# USB_RS232_Adaper_V2.net
KiCad netlist of a schematic drawn in EAGLE
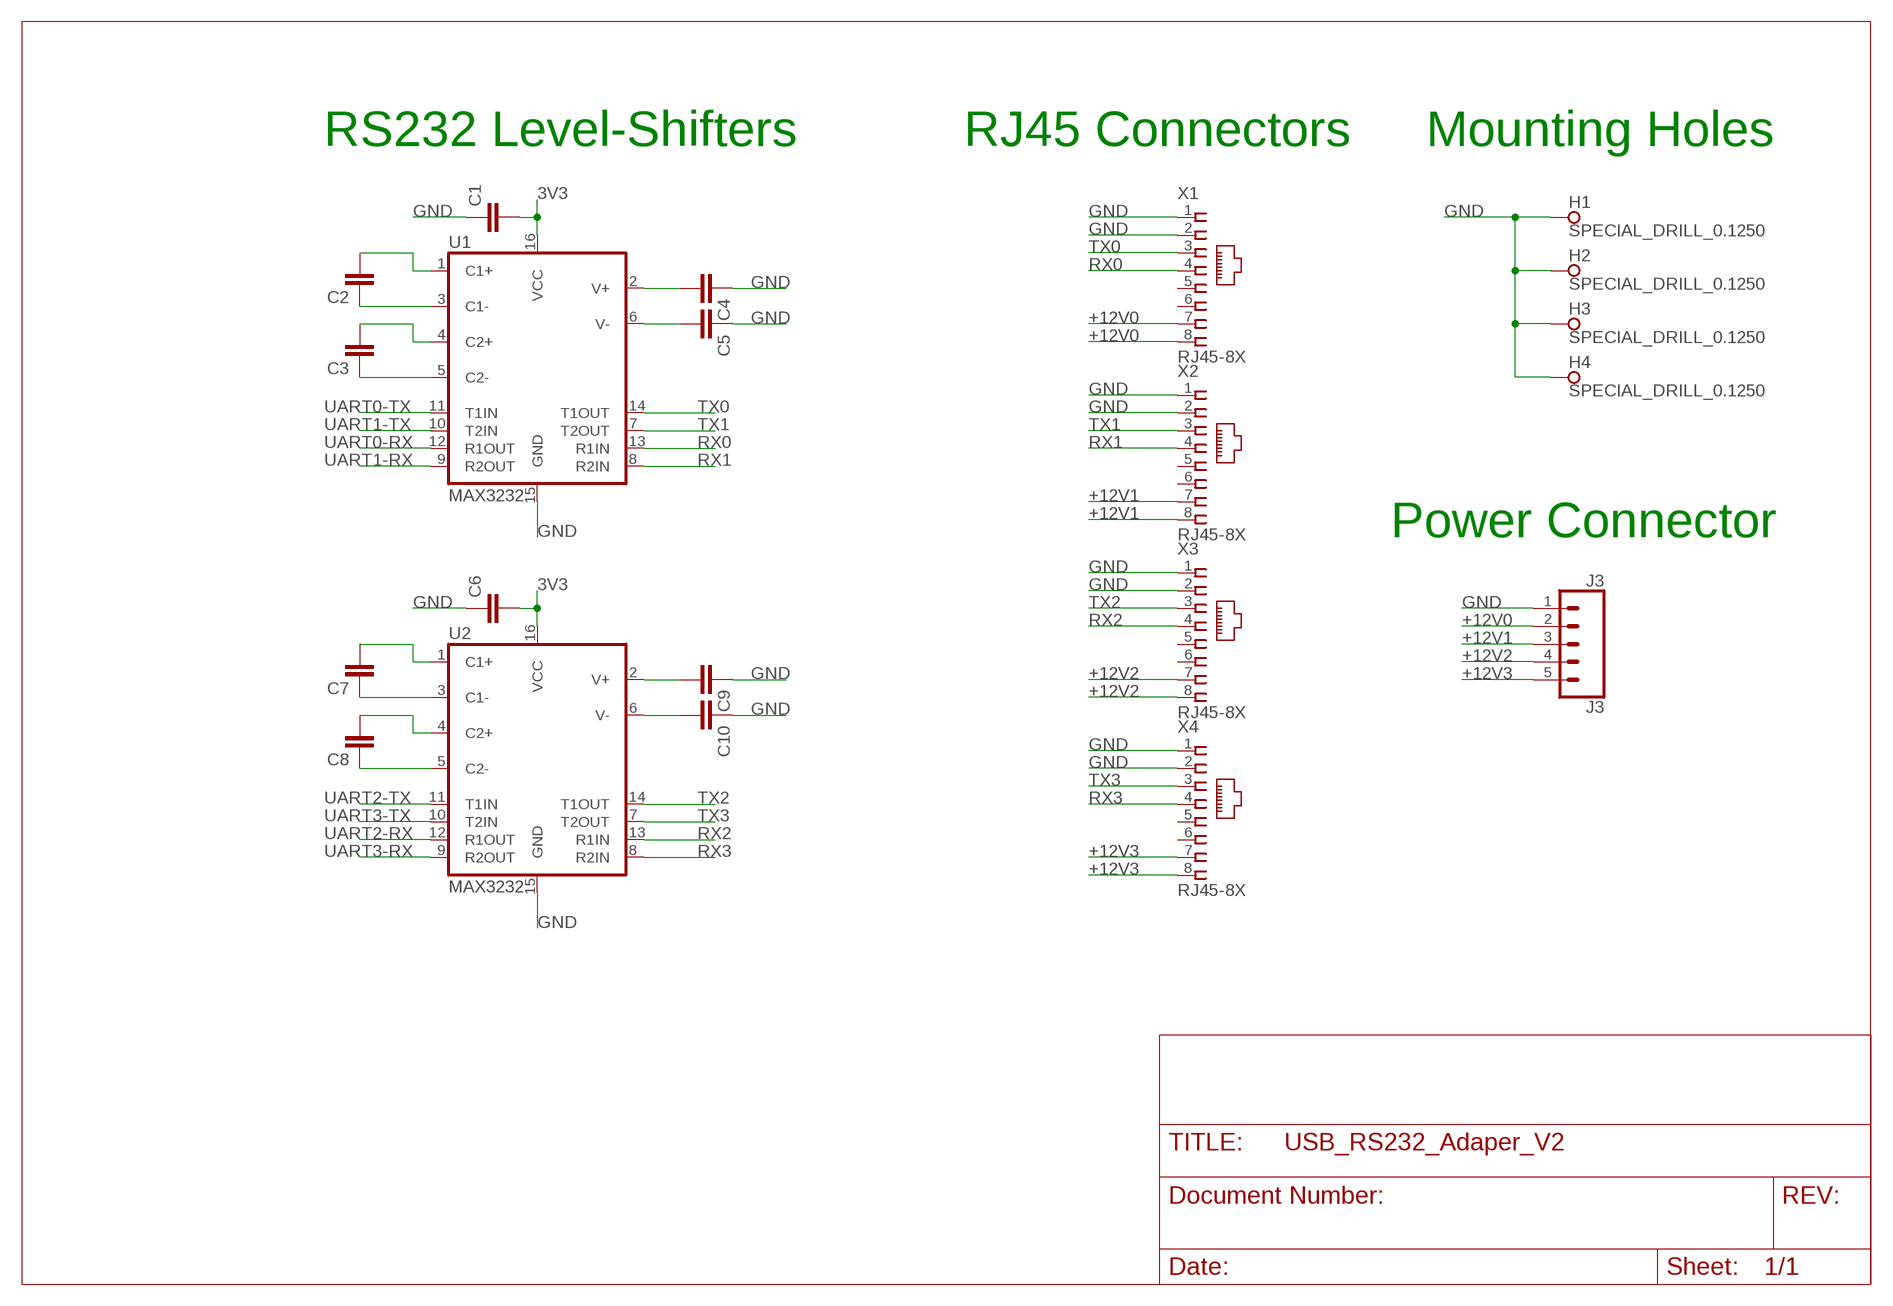
[diagram p0: schematic, sheet 1, part 1 of 2]
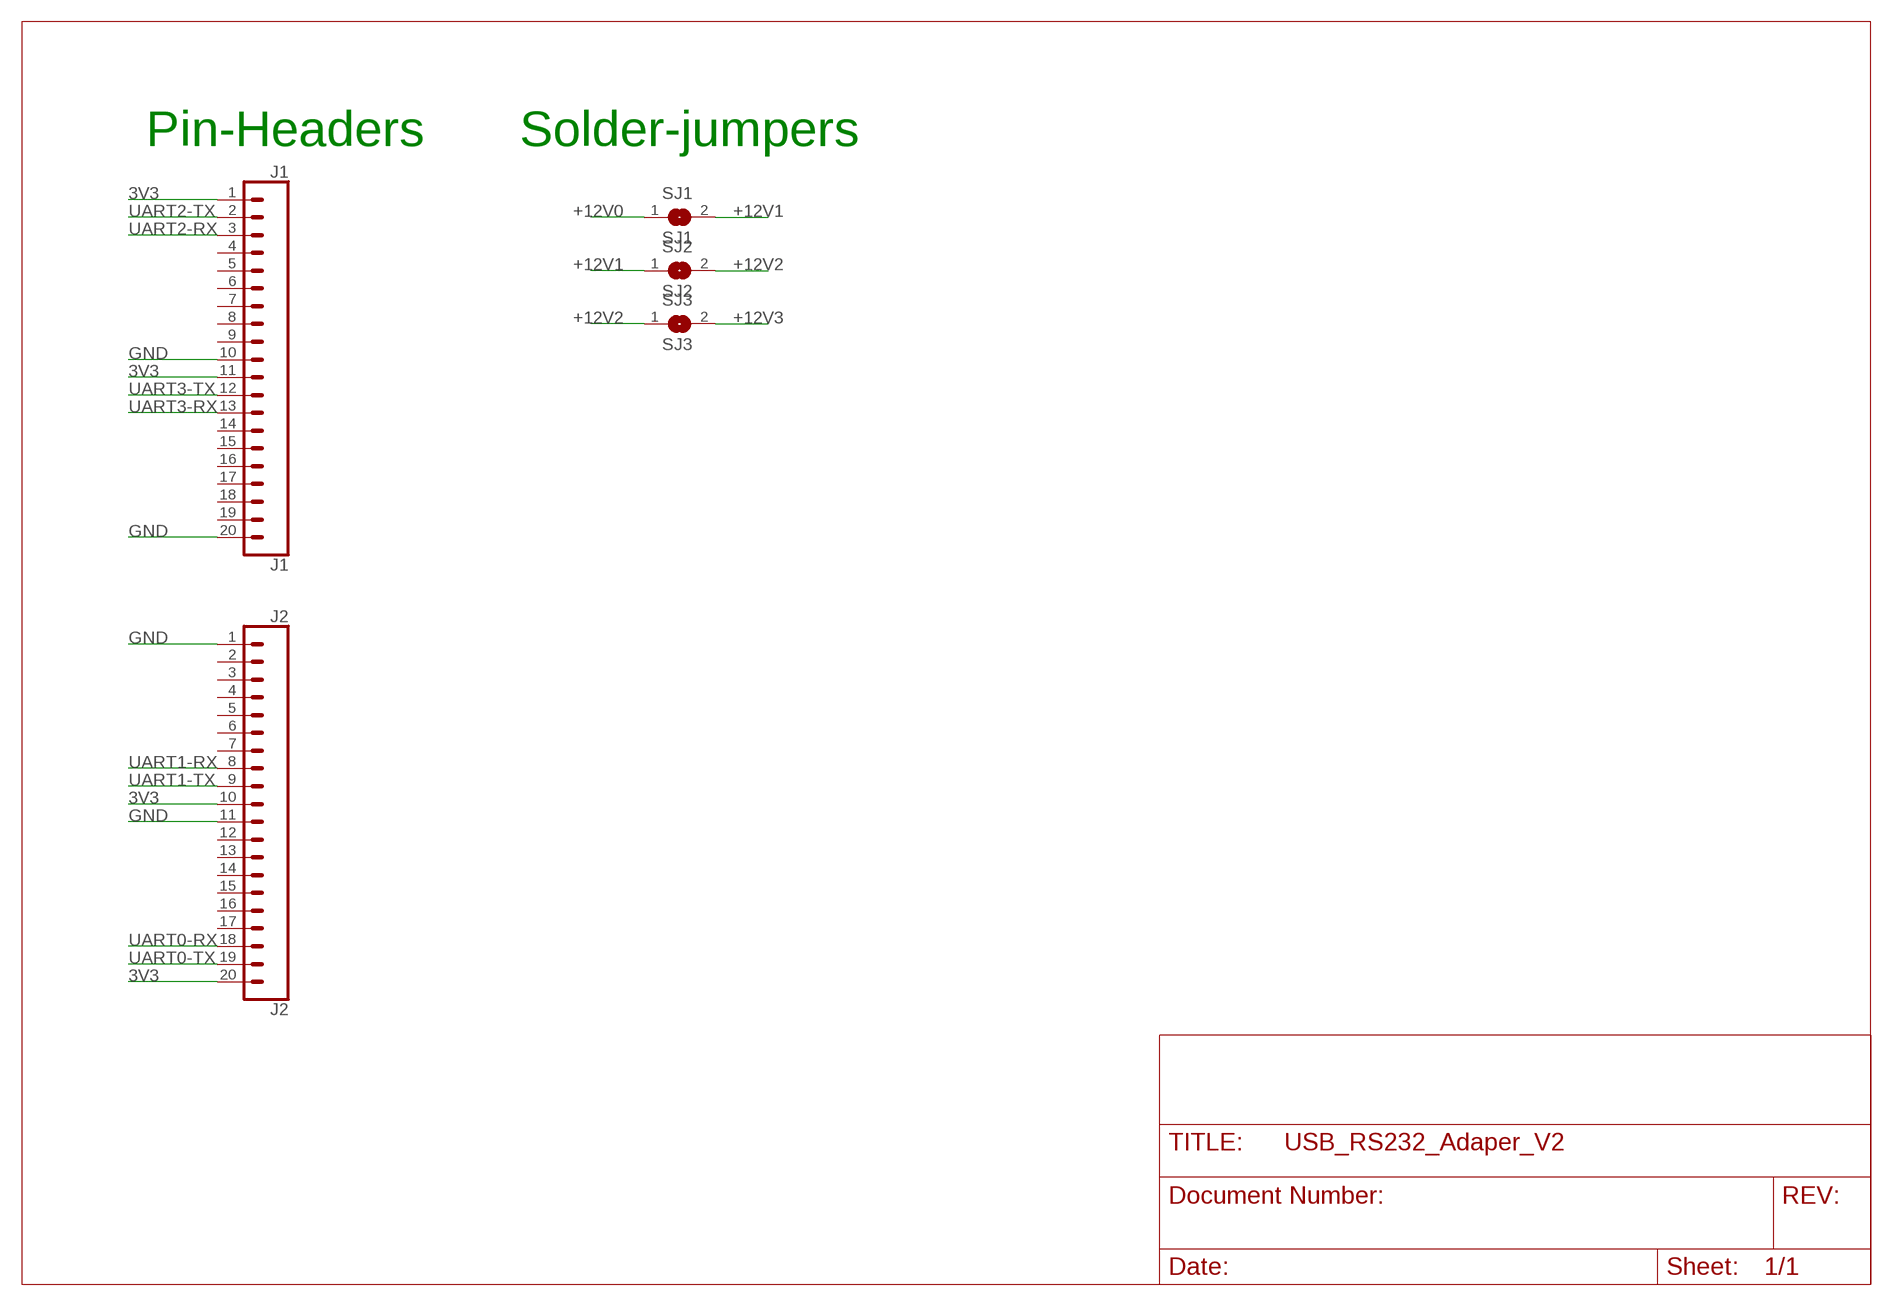
[diagram p1: schematic, sheet 1, part 2 of 2]

(export (version "E")
  (design (tool "Eeschema 10.0.6"))
  (components
    (comp (ref "C1")
      (value "0.1uF")
      (footprint "eagle-import:0805")
      (libsource (lib "eagle-import") (part "CAP-0805"))
    )
    (comp (ref "C2")
      (value "0.1uF")
      (footprint "eagle-import:0805")
      (libsource (lib "eagle-import") (part "CAP-0805"))
    )
    (comp (ref "C3")
      (value "0.1uF")
      (footprint "eagle-import:0805")
      (libsource (lib "eagle-import") (part "CAP-0805"))
    )
    (comp (ref "C4")
      (value "0.1uF")
      (footprint "eagle-import:0805")
      (libsource (lib "eagle-import") (part "CAP-0805"))
    )
    (comp (ref "C5")
      (value "0.1uF")
      (footprint "eagle-import:0805")
      (libsource (lib "eagle-import") (part "CAP-0805"))
    )
    (comp (ref "C6")
      (value "0.1uF")
      (footprint "eagle-import:0805")
      (libsource (lib "eagle-import") (part "CAP-0805"))
    )
    (comp (ref "C7")
      (value "0.1uF")
      (footprint "eagle-import:0805")
      (libsource (lib "eagle-import") (part "CAP-0805"))
    )
    (comp (ref "C8")
      (value "0.1uF")
      (footprint "eagle-import:0805")
      (libsource (lib "eagle-import") (part "CAP-0805"))
    )
    (comp (ref "C9")
      (value "0.1uF")
      (footprint "eagle-import:0805")
      (libsource (lib "eagle-import") (part "CAP-0805"))
    )
    (comp (ref "C10")
      (value "0.1uF")
      (footprint "eagle-import:0805")
      (libsource (lib "eagle-import") (part "CAP-0805"))
    )
    (comp (ref "H1")
      (value "SPECIAL_DRILL_0.1250")
      (footprint "eagle-import:PAD_0.1250")
      (libsource (lib "eagle-import") (part "SPECIAL_DRILL_0.1250"))
    )
    (comp (ref "H2")
      (value "SPECIAL_DRILL_0.1250")
      (footprint "eagle-import:PAD_0.1250")
      (libsource (lib "eagle-import") (part "SPECIAL_DRILL_0.1250"))
    )
    (comp (ref "H3")
      (value "SPECIAL_DRILL_0.1250")
      (footprint "eagle-import:PAD_0.1250")
      (libsource (lib "eagle-import") (part "SPECIAL_DRILL_0.1250"))
    )
    (comp (ref "H4")
      (value "SPECIAL_DRILL_0.1250")
      (footprint "eagle-import:PAD_0.1250")
      (libsource (lib "eagle-import") (part "SPECIAL_DRILL_0.1250"))
    )
    (comp (ref "J1")
      (value "J1")
      (footprint "eagle-import:1X20")
      (libsource (lib "eagle-import") (part "CONN_20"))
    )
    (comp (ref "J2")
      (value "J2")
      (footprint "eagle-import:1X20")
      (libsource (lib "eagle-import") (part "CONN_20"))
    )
    (comp (ref "J3")
      (value "J3")
      (footprint "eagle-import:1X05")
      (libsource (lib "eagle-import") (part "CONN_05"))
    )
    (comp (ref "SJ1")
      (value "SJ1")
      (footprint "eagle-import:SJ")
      (libsource (lib "eagle-import") (part "SJ"))
    )
    (comp (ref "SJ2")
      (value "SJ2")
      (footprint "eagle-import:SJ")
      (libsource (lib "eagle-import") (part "SJ"))
    )
    (comp (ref "SJ3")
      (value "SJ3")
      (footprint "eagle-import:SJ")
      (libsource (lib "eagle-import") (part "SJ"))
    )
    (comp (ref "U1")
      (value "MAX3232")
      (footprint "eagle-import:SO16")
      (libsource (lib "eagle-import") (part "MAX2323SOIC16"))
    )
    (comp (ref "U2")
      (value "MAX3232")
      (footprint "eagle-import:SO16")
      (libsource (lib "eagle-import") (part "MAX2323SOIC16"))
    )
    (comp (ref "X1")
      (value "RJ45-8X")
      (footprint "eagle-import:RJ45-NO-SHIELD")
      (libsource (lib "eagle-import") (part "RJ45-8X"))
    )
    (comp (ref "X2")
      (value "RJ45-8X")
      (footprint "eagle-import:RJ45-NO-SHIELD")
      (libsource (lib "eagle-import") (part "RJ45-8X"))
    )
    (comp (ref "X3")
      (value "RJ45-8X")
      (footprint "eagle-import:RJ45-NO-SHIELD")
      (libsource (lib "eagle-import") (part "RJ45-8X"))
    )
    (comp (ref "X4")
      (value "RJ45-8X")
      (footprint "eagle-import:RJ45-NO-SHIELD")
      (libsource (lib "eagle-import") (part "RJ45-8X"))
    )
  )
  (nets
    (net (code "1") (name "/+12V0") (class "Default")
      (node (ref "J3") (pin "2") (pinfunction "2_2") (pintype "passive"))
      (node (ref "SJ1") (pin "1") (pinfunction "1_1") (pintype "passive"))
      (node (ref "X1") (pin "7") (pinfunction "7_7") (pintype "passive"))
      (node (ref "X1") (pin "8") (pinfunction "8_8") (pintype "passive"))
    )
    (net (code "2") (name "/+12V1") (class "Default")
      (node (ref "J3") (pin "3") (pinfunction "3_3") (pintype "passive"))
      (node (ref "SJ1") (pin "2") (pinfunction "2_2") (pintype "passive"))
      (node (ref "SJ2") (pin "1") (pinfunction "1_1") (pintype "passive"))
      (node (ref "X2") (pin "7") (pinfunction "7_7") (pintype "passive"))
      (node (ref "X2") (pin "8") (pinfunction "8_8") (pintype "passive"))
    )
    (net (code "3") (name "/+12V2") (class "Default")
      (node (ref "J3") (pin "4") (pinfunction "4_4") (pintype "passive"))
      (node (ref "SJ2") (pin "2") (pinfunction "2_2") (pintype "passive"))
      (node (ref "SJ3") (pin "1") (pinfunction "1_1") (pintype "passive"))
      (node (ref "X3") (pin "7") (pinfunction "7_7") (pintype "passive"))
      (node (ref "X3") (pin "8") (pinfunction "8_8") (pintype "passive"))
    )
    (net (code "4") (name "/+12V3") (class "Default")
      (node (ref "J3") (pin "5") (pinfunction "5_5") (pintype "passive"))
      (node (ref "SJ3") (pin "2") (pinfunction "2_2") (pintype "passive"))
      (node (ref "X4") (pin "7") (pinfunction "7_7") (pintype "passive"))
      (node (ref "X4") (pin "8") (pinfunction "8_8") (pintype "passive"))
    )
    (net (code "5") (name "/3V3") (class "Default")
      (node (ref "C1") (pin "2") (pinfunction "2_2") (pintype "passive"))
      (node (ref "C6") (pin "2") (pinfunction "2_2") (pintype "passive"))
      (node (ref "J1") (pin "1") (pinfunction "1_1") (pintype "passive"))
      (node (ref "J1") (pin "11") (pinfunction "11_11") (pintype "passive"))
      (node (ref "J2") (pin "10") (pinfunction "10_10") (pintype "passive"))
      (node (ref "J2") (pin "20") (pinfunction "20_20") (pintype "passive"))
      (node (ref "U1") (pin "16") (pinfunction "VCC_16") (pintype "bidirectional"))
      (node (ref "U2") (pin "16") (pinfunction "VCC_16") (pintype "bidirectional"))
    )
    (net (code "6") (name "/GND") (class "Default")
      (node (ref "C1") (pin "1") (pinfunction "1_1") (pintype "passive"))
      (node (ref "C10") (pin "1") (pinfunction "1_1") (pintype "passive"))
      (node (ref "C4") (pin "1") (pinfunction "1_1") (pintype "passive"))
      (node (ref "C5") (pin "1") (pinfunction "1_1") (pintype "passive"))
      (node (ref "C6") (pin "1") (pinfunction "1_1") (pintype "passive"))
      (node (ref "C9") (pin "1") (pinfunction "1_1") (pintype "passive"))
      (node (ref "H1") (pin "1") (pinfunction "1_1") (pintype "passive"))
      (node (ref "H2") (pin "1") (pinfunction "1_1") (pintype "passive"))
      (node (ref "H3") (pin "1") (pinfunction "1_1") (pintype "passive"))
      (node (ref "H4") (pin "1") (pinfunction "1_1") (pintype "passive"))
      (node (ref "J1") (pin "10") (pinfunction "10_10") (pintype "passive"))
      (node (ref "J1") (pin "20") (pinfunction "20_20") (pintype "passive"))
      (node (ref "J2") (pin "1") (pinfunction "1_1") (pintype "passive"))
      (node (ref "J2") (pin "11") (pinfunction "11_11") (pintype "passive"))
      (node (ref "J3") (pin "1") (pinfunction "1_1") (pintype "passive"))
      (node (ref "U1") (pin "15") (pinfunction "GND_15") (pintype "bidirectional"))
      (node (ref "U2") (pin "15") (pinfunction "GND_15") (pintype "bidirectional"))
      (node (ref "X1") (pin "1") (pinfunction "1_1") (pintype "passive"))
      (node (ref "X1") (pin "2") (pinfunction "2_2") (pintype "passive"))
      (node (ref "X2") (pin "1") (pinfunction "1_1") (pintype "passive"))
      (node (ref "X2") (pin "2") (pinfunction "2_2") (pintype "passive"))
      (node (ref "X3") (pin "1") (pinfunction "1_1") (pintype "passive"))
      (node (ref "X3") (pin "2") (pinfunction "2_2") (pintype "passive"))
      (node (ref "X4") (pin "1") (pinfunction "1_1") (pintype "passive"))
      (node (ref "X4") (pin "2") (pinfunction "2_2") (pintype "passive"))
    )
    (net (code "7") (name "/RX0") (class "Default")
      (node (ref "U1") (pin "13") (pinfunction "R1IN_13") (pintype "input"))
      (node (ref "X1") (pin "4") (pinfunction "4_4") (pintype "passive"))
    )
    (net (code "8") (name "/RX1") (class "Default")
      (node (ref "U1") (pin "8") (pinfunction "R2IN_8") (pintype "input"))
      (node (ref "X2") (pin "4") (pinfunction "4_4") (pintype "passive"))
    )
    (net (code "9") (name "/RX2") (class "Default")
      (node (ref "U2") (pin "13") (pinfunction "R1IN_13") (pintype "input"))
      (node (ref "X3") (pin "4") (pinfunction "4_4") (pintype "passive"))
    )
    (net (code "10") (name "/RX3") (class "Default")
      (node (ref "U2") (pin "8") (pinfunction "R2IN_8") (pintype "input"))
      (node (ref "X4") (pin "4") (pinfunction "4_4") (pintype "passive"))
    )
    (net (code "11") (name "/TX0") (class "Default")
      (node (ref "U1") (pin "14") (pinfunction "T1OUT_14") (pintype "output"))
      (node (ref "X1") (pin "3") (pinfunction "3_3") (pintype "passive"))
    )
    (net (code "12") (name "/TX1") (class "Default")
      (node (ref "U1") (pin "7") (pinfunction "T2OUT_7") (pintype "output"))
      (node (ref "X2") (pin "3") (pinfunction "3_3") (pintype "passive"))
    )
    (net (code "13") (name "/TX2") (class "Default")
      (node (ref "U2") (pin "14") (pinfunction "T1OUT_14") (pintype "output"))
      (node (ref "X3") (pin "3") (pinfunction "3_3") (pintype "passive"))
    )
    (net (code "14") (name "/TX3") (class "Default")
      (node (ref "U2") (pin "7") (pinfunction "T2OUT_7") (pintype "output"))
      (node (ref "X4") (pin "3") (pinfunction "3_3") (pintype "passive"))
    )
    (net (code "15") (name "/UART0-RX") (class "Default")
      (node (ref "J2") (pin "18") (pinfunction "18_18") (pintype "passive"))
      (node (ref "U1") (pin "12") (pinfunction "R1OUT_12") (pintype "output"))
    )
    (net (code "16") (name "/UART0-TX") (class "Default")
      (node (ref "J2") (pin "19") (pinfunction "19_19") (pintype "passive"))
      (node (ref "U1") (pin "11") (pinfunction "T1IN_11") (pintype "input"))
    )
    (net (code "17") (name "/UART1-RX") (class "Default")
      (node (ref "J2") (pin "8") (pinfunction "8_8") (pintype "passive"))
      (node (ref "U1") (pin "9") (pinfunction "R2OUT_9") (pintype "output"))
    )
    (net (code "18") (name "/UART1-TX") (class "Default")
      (node (ref "J2") (pin "9") (pinfunction "9_9") (pintype "passive"))
      (node (ref "U1") (pin "10") (pinfunction "T2IN_10") (pintype "input"))
    )
    (net (code "19") (name "/UART2-RX") (class "Default")
      (node (ref "J1") (pin "3") (pinfunction "3_3") (pintype "passive"))
      (node (ref "U2") (pin "12") (pinfunction "R1OUT_12") (pintype "output"))
    )
    (net (code "20") (name "/UART2-TX") (class "Default")
      (node (ref "J1") (pin "2") (pinfunction "2_2") (pintype "passive"))
      (node (ref "U2") (pin "11") (pinfunction "T1IN_11") (pintype "input"))
    )
    (net (code "21") (name "/UART3-RX") (class "Default")
      (node (ref "J1") (pin "13") (pinfunction "13_13") (pintype "passive"))
      (node (ref "U2") (pin "9") (pinfunction "R2OUT_9") (pintype "output"))
    )
    (net (code "22") (name "/UART3-TX") (class "Default")
      (node (ref "J1") (pin "12") (pinfunction "12_12") (pintype "passive"))
      (node (ref "U2") (pin "10") (pinfunction "T2IN_10") (pintype "input"))
    )
    (net (code "23") (name "Net-(U1-C1+)") (class "Default")
      (node (ref "C2") (pin "2") (pinfunction "2_2") (pintype "passive"))
      (node (ref "U1") (pin "1") (pinfunction "C1+_1") (pintype "bidirectional"))
    )
    (net (code "24") (name "Net-(U1-C1-)") (class "Default")
      (node (ref "C2") (pin "1") (pinfunction "1_1") (pintype "passive"))
      (node (ref "U1") (pin "3") (pinfunction "C1-_3") (pintype "bidirectional"))
    )
    (net (code "25") (name "Net-(U1-C2+)") (class "Default")
      (node (ref "C3") (pin "2") (pinfunction "2_2") (pintype "passive"))
      (node (ref "U1") (pin "4") (pinfunction "C2+_4") (pintype "bidirectional"))
    )
    (net (code "26") (name "Net-(U1-C2-)") (class "Default")
      (node (ref "C3") (pin "1") (pinfunction "1_1") (pintype "passive"))
      (node (ref "U1") (pin "5") (pinfunction "C2-_5") (pintype "bidirectional"))
    )
    (net (code "27") (name "Net-(U1-V+)") (class "Default")
      (node (ref "C4") (pin "2") (pinfunction "2_2") (pintype "passive"))
      (node (ref "U1") (pin "2") (pinfunction "V+_2") (pintype "bidirectional"))
    )
    (net (code "28") (name "Net-(U1-V-)") (class "Default")
      (node (ref "C5") (pin "2") (pinfunction "2_2") (pintype "passive"))
      (node (ref "U1") (pin "6") (pinfunction "V-_6") (pintype "bidirectional"))
    )
    (net (code "29") (name "Net-(U2-C1+)") (class "Default")
      (node (ref "C7") (pin "2") (pinfunction "2_2") (pintype "passive"))
      (node (ref "U2") (pin "1") (pinfunction "C1+_1") (pintype "bidirectional"))
    )
    (net (code "30") (name "Net-(U2-C1-)") (class "Default")
      (node (ref "C7") (pin "1") (pinfunction "1_1") (pintype "passive"))
      (node (ref "U2") (pin "3") (pinfunction "C1-_3") (pintype "bidirectional"))
    )
    (net (code "31") (name "Net-(U2-C2+)") (class "Default")
      (node (ref "C8") (pin "2") (pinfunction "2_2") (pintype "passive"))
      (node (ref "U2") (pin "4") (pinfunction "C2+_4") (pintype "bidirectional"))
    )
    (net (code "32") (name "Net-(U2-C2-)") (class "Default")
      (node (ref "C8") (pin "1") (pinfunction "1_1") (pintype "passive"))
      (node (ref "U2") (pin "5") (pinfunction "C2-_5") (pintype "bidirectional"))
    )
    (net (code "33") (name "Net-(U2-V+)") (class "Default")
      (node (ref "C9") (pin "2") (pinfunction "2_2") (pintype "passive"))
      (node (ref "U2") (pin "2") (pinfunction "V+_2") (pintype "bidirectional"))
    )
    (net (code "34") (name "Net-(U2-V-)") (class "Default")
      (node (ref "C10") (pin "2") (pinfunction "2_2") (pintype "passive"))
      (node (ref "U2") (pin "6") (pinfunction "V-_6") (pintype "bidirectional"))
    )
    (net (code "35") (name "unconnected-(J1-Pad4)") (class "Default")
      (node (ref "J1") (pin "4") (pinfunction "4_4") (pintype "passive"))
    )
    (net (code "36") (name "unconnected-(J1-Pad5)") (class "Default")
      (node (ref "J1") (pin "5") (pinfunction "5_5") (pintype "passive"))
    )
    (net (code "37") (name "unconnected-(J1-Pad6)") (class "Default")
      (node (ref "J1") (pin "6") (pinfunction "6_6") (pintype "passive"))
    )
    (net (code "38") (name "unconnected-(J1-Pad7)") (class "Default")
      (node (ref "J1") (pin "7") (pinfunction "7_7") (pintype "passive"))
    )
    (net (code "39") (name "unconnected-(J1-Pad8)") (class "Default")
      (node (ref "J1") (pin "8") (pinfunction "8_8") (pintype "passive"))
    )
    (net (code "40") (name "unconnected-(J1-Pad9)") (class "Default")
      (node (ref "J1") (pin "9") (pinfunction "9_9") (pintype "passive"))
    )
    (net (code "41") (name "unconnected-(J1-Pad14)") (class "Default")
      (node (ref "J1") (pin "14") (pinfunction "14_14") (pintype "passive"))
    )
    (net (code "42") (name "unconnected-(J1-Pad15)") (class "Default")
      (node (ref "J1") (pin "15") (pinfunction "15_15") (pintype "passive"))
    )
    (net (code "43") (name "unconnected-(J1-Pad16)") (class "Default")
      (node (ref "J1") (pin "16") (pinfunction "16_16") (pintype "passive"))
    )
    (net (code "44") (name "unconnected-(J1-Pad17)") (class "Default")
      (node (ref "J1") (pin "17") (pinfunction "17_17") (pintype "passive"))
    )
    (net (code "45") (name "unconnected-(J1-Pad18)") (class "Default")
      (node (ref "J1") (pin "18") (pinfunction "18_18") (pintype "passive"))
    )
    (net (code "46") (name "unconnected-(J1-Pad19)") (class "Default")
      (node (ref "J1") (pin "19") (pinfunction "19_19") (pintype "passive"))
    )
    (net (code "47") (name "unconnected-(J2-Pad2)") (class "Default")
      (node (ref "J2") (pin "2") (pinfunction "2_2") (pintype "passive"))
    )
    (net (code "48") (name "unconnected-(J2-Pad3)") (class "Default")
      (node (ref "J2") (pin "3") (pinfunction "3_3") (pintype "passive"))
    )
    (net (code "49") (name "unconnected-(J2-Pad4)") (class "Default")
      (node (ref "J2") (pin "4") (pinfunction "4_4") (pintype "passive"))
    )
    (net (code "50") (name "unconnected-(J2-Pad5)") (class "Default")
      (node (ref "J2") (pin "5") (pinfunction "5_5") (pintype "passive"))
    )
    (net (code "51") (name "unconnected-(J2-Pad6)") (class "Default")
      (node (ref "J2") (pin "6") (pinfunction "6_6") (pintype "passive"))
    )
    (net (code "52") (name "unconnected-(J2-Pad7)") (class "Default")
      (node (ref "J2") (pin "7") (pinfunction "7_7") (pintype "passive"))
    )
    (net (code "53") (name "unconnected-(J2-Pad12)") (class "Default")
      (node (ref "J2") (pin "12") (pinfunction "12_12") (pintype "passive"))
    )
    (net (code "54") (name "unconnected-(J2-Pad13)") (class "Default")
      (node (ref "J2") (pin "13") (pinfunction "13_13") (pintype "passive"))
    )
    (net (code "55") (name "unconnected-(J2-Pad14)") (class "Default")
      (node (ref "J2") (pin "14") (pinfunction "14_14") (pintype "passive"))
    )
    (net (code "56") (name "unconnected-(J2-Pad15)") (class "Default")
      (node (ref "J2") (pin "15") (pinfunction "15_15") (pintype "passive"))
    )
    (net (code "57") (name "unconnected-(J2-Pad16)") (class "Default")
      (node (ref "J2") (pin "16") (pinfunction "16_16") (pintype "passive"))
    )
    (net (code "58") (name "unconnected-(J2-Pad17)") (class "Default")
      (node (ref "J2") (pin "17") (pinfunction "17_17") (pintype "passive"))
    )
    (net (code "59") (name "unconnected-(X1-Pad5)") (class "Default")
      (node (ref "X1") (pin "5") (pinfunction "5_5") (pintype "passive"))
    )
    (net (code "60") (name "unconnected-(X1-Pad6)") (class "Default")
      (node (ref "X1") (pin "6") (pinfunction "6_6") (pintype "passive"))
    )
    (net (code "61") (name "unconnected-(X2-Pad5)") (class "Default")
      (node (ref "X2") (pin "5") (pinfunction "5_5") (pintype "passive"))
    )
    (net (code "62") (name "unconnected-(X2-Pad6)") (class "Default")
      (node (ref "X2") (pin "6") (pinfunction "6_6") (pintype "passive"))
    )
    (net (code "63") (name "unconnected-(X3-Pad5)") (class "Default")
      (node (ref "X3") (pin "5") (pinfunction "5_5") (pintype "passive"))
    )
    (net (code "64") (name "unconnected-(X3-Pad6)") (class "Default")
      (node (ref "X3") (pin "6") (pinfunction "6_6") (pintype "passive"))
    )
    (net (code "65") (name "unconnected-(X4-Pad5)") (class "Default")
      (node (ref "X4") (pin "5") (pinfunction "5_5") (pintype "passive"))
    )
    (net (code "66") (name "unconnected-(X4-Pad6)") (class "Default")
      (node (ref "X4") (pin "6") (pinfunction "6_6") (pintype "passive"))
    )
  )
)
